# rda5708m.net
KiCad netlist of a schematic drawn in EAGLE
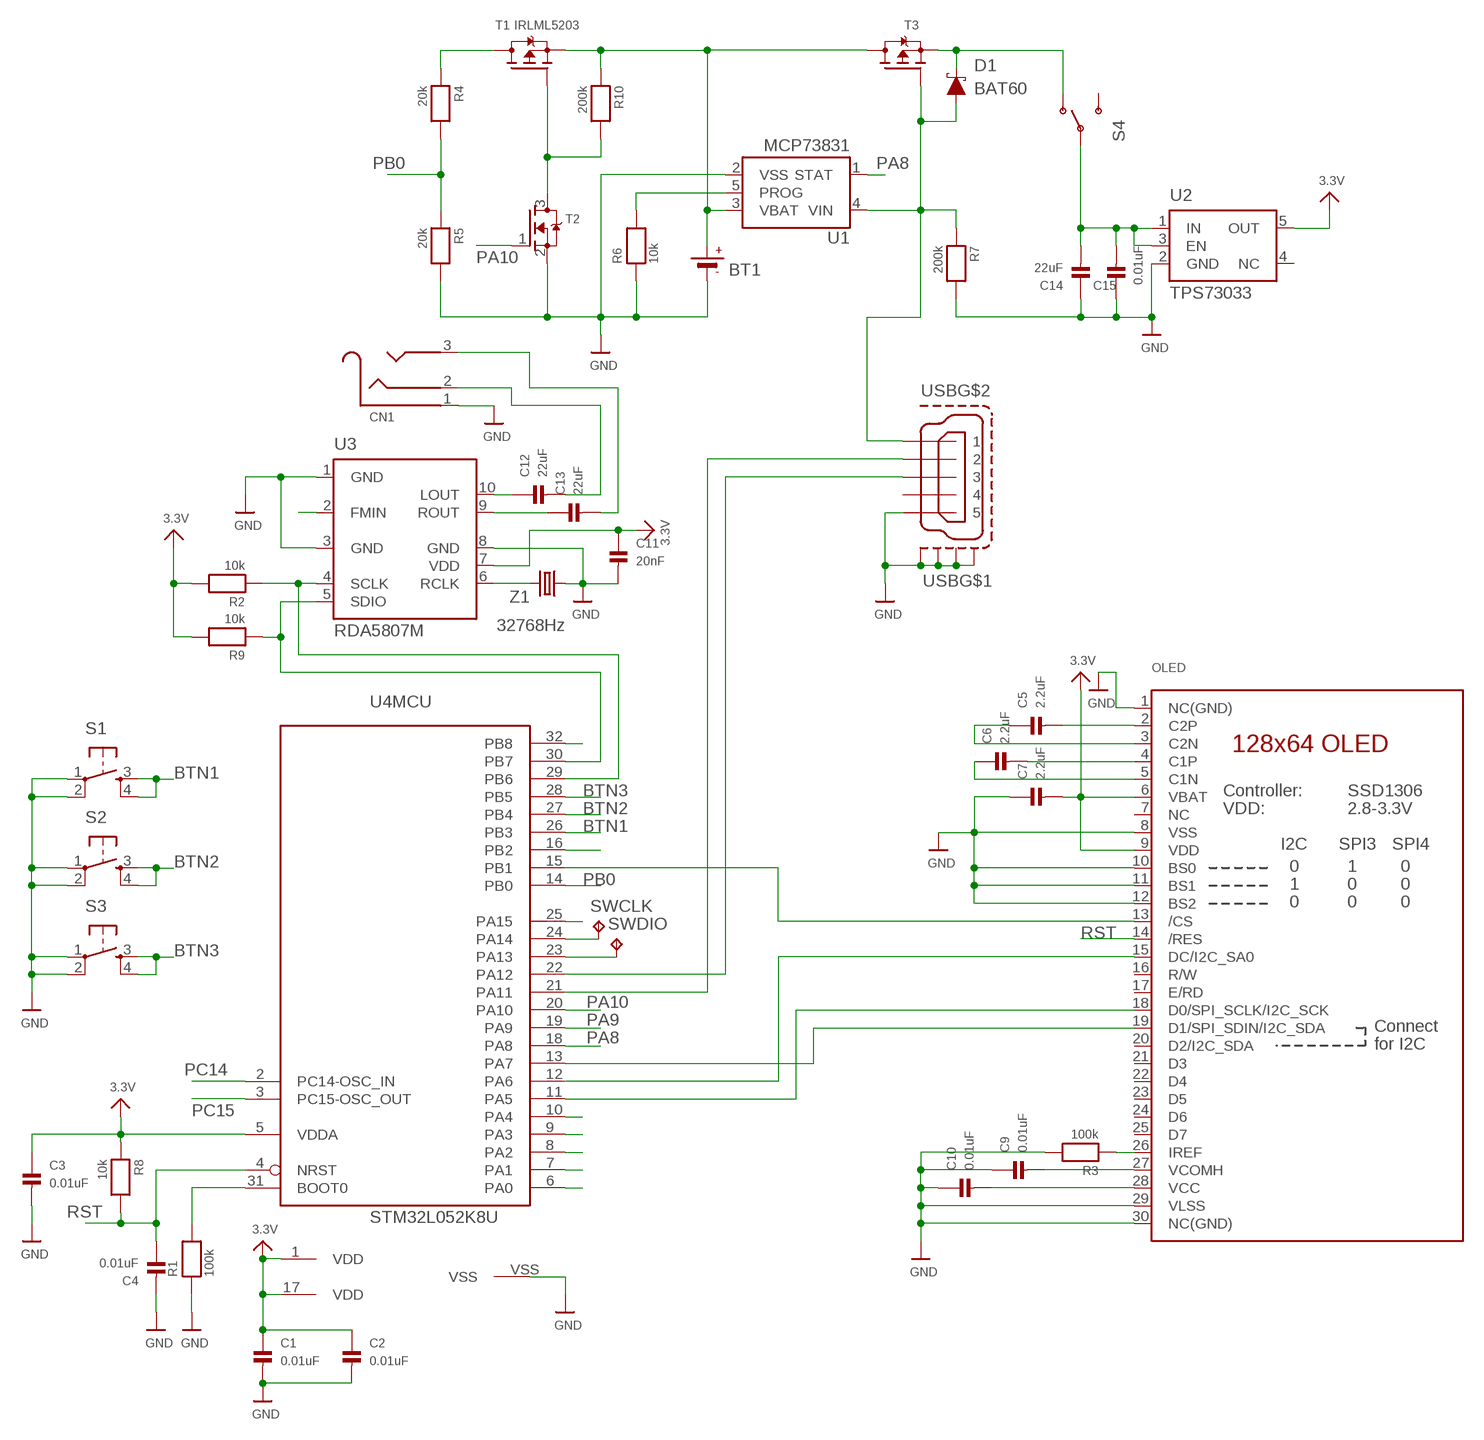
[diagram p0: schematic, sheet 1]

(export (version "E")
  (design (tool "Eeschema 10.0.6"))
  (components
    (comp (ref "BT1")
      (value "LiPo 4.2V")
      (footprint "eagle-import:JSTPH2")
      (libsource (lib "eagle-import") (part "BATTERY"))
    )
    (comp (ref "C1")
      (value "0.01uF")
      (footprint "eagle-import:0603")
      (libsource (lib "eagle-import") (part "CAP_CERAMIC0603"))
    )
    (comp (ref "C2")
      (value "0.01uF")
      (footprint "eagle-import:0603")
      (libsource (lib "eagle-import") (part "CAP_CERAMIC0603"))
    )
    (comp (ref "C3")
      (value "0.01uF")
      (footprint "eagle-import:0603")
      (libsource (lib "eagle-import") (part "CAP_CERAMIC0603"))
    )
    (comp (ref "C4")
      (value "0.01uF")
      (footprint "eagle-import:0603")
      (libsource (lib "eagle-import") (part "CAP_CERAMIC0603"))
    )
    (comp (ref "C5")
      (value "2.2uF")
      (footprint "eagle-import:0603")
      (libsource (lib "eagle-import") (part "CAP_CERAMIC0603"))
    )
    (comp (ref "C6")
      (value "2.2uF")
      (footprint "eagle-import:0603")
      (libsource (lib "eagle-import") (part "CAP_CERAMIC0603"))
    )
    (comp (ref "C7")
      (value "2.2uF")
      (footprint "eagle-import:0603")
      (libsource (lib "eagle-import") (part "CAP_CERAMIC0603"))
    )
    (comp (ref "C9")
      (value "0.01uF")
      (footprint "eagle-import:0603")
      (libsource (lib "eagle-import") (part "CAP_CERAMIC0603"))
    )
    (comp (ref "C10")
      (value "0.01uF")
      (footprint "eagle-import:0603")
      (libsource (lib "eagle-import") (part "CAP_CERAMIC0603"))
    )
    (comp (ref "C11")
      (value "20nF")
      (footprint "eagle-import:0603")
      (libsource (lib "eagle-import") (part "CAP_CERAMIC0603"))
    )
    (comp (ref "C12")
      (value "22uF")
      (footprint "eagle-import:0805")
      (libsource (lib "eagle-import") (part "CAP_CERAMIC0805"))
    )
    (comp (ref "C13")
      (value "22uF")
      (footprint "eagle-import:0805")
      (libsource (lib "eagle-import") (part "CAP_CERAMIC0805"))
    )
    (comp (ref "C14")
      (value "22uF")
      (footprint "eagle-import:0805")
      (libsource (lib "eagle-import") (part "CAP_CERAMIC0805"))
    )
    (comp (ref "C15")
      (value "0.01uF")
      (footprint "eagle-import:0603")
      (libsource (lib "eagle-import") (part "CAP_CERAMIC0603"))
    )
    (comp (ref "CN1")
      (value "AUDIO_3.5JACK")
      (footprint "eagle-import:AUDIO_3.5")
      (libsource (lib "eagle-import") (part "AUDIO_3.5JACK"))
    )
    (comp (ref "D1")
      (value "BAT60")
      (footprint "eagle-import:SOD-323")
      (libsource (lib "eagle-import") (part "DIODE-SCHOTTKY-BAT20J"))
    )
    (comp (ref "OLED")
      (value "DISP_OLED_UG-2864HSWEG012SIDE")
      (footprint "eagle-import:OLED0.96")
      (libsource (lib "eagle-import") (part "DISP_OLED_UG-2864HSWEG012SIDE"))
    )
    (comp (ref "R1")
      (value "100k")
      (footprint "eagle-import:0603")
      (libsource (lib "eagle-import") (part "RESISTOR0603"))
    )
    (comp (ref "R2")
      (value "10k")
      (footprint "eagle-import:0603")
      (libsource (lib "eagle-import") (part "RESISTOR0603"))
    )
    (comp (ref "R3")
      (value "100k")
      (footprint "eagle-import:0603")
      (libsource (lib "eagle-import") (part "RESISTOR0603"))
    )
    (comp (ref "R4")
      (value "20k")
      (footprint "eagle-import:0603")
      (libsource (lib "eagle-import") (part "RESISTOR0603"))
    )
    (comp (ref "R5")
      (value "20k")
      (footprint "eagle-import:0603")
      (libsource (lib "eagle-import") (part "RESISTOR0603"))
    )
    (comp (ref "R6")
      (value "10k")
      (footprint "eagle-import:0603")
      (libsource (lib "eagle-import") (part "RESISTOR0603"))
    )
    (comp (ref "R7")
      (value "200k")
      (footprint "eagle-import:0603")
      (libsource (lib "eagle-import") (part "RESISTOR0603"))
    )
    (comp (ref "R8")
      (value "10k")
      (footprint "eagle-import:0603")
      (libsource (lib "eagle-import") (part "RESISTOR0603"))
    )
    (comp (ref "R9")
      (value "10k")
      (footprint "eagle-import:0603")
      (libsource (lib "eagle-import") (part "RESISTOR0603"))
    )
    (comp (ref "R10")
      (value "200k")
      (footprint "eagle-import:0603")
      (libsource (lib "eagle-import") (part "RESISTOR0603"))
    )
    (comp (ref "S1")
      (value "TAC_SWITCH")
      (footprint "eagle-import:TACTILE-SWITCH-SMD45")
      (libsource (lib "eagle-import") (part "TAC_SWITCH"))
    )
    (comp (ref "S2")
      (value "TAC_SWITCH")
      (footprint "eagle-import:TACTILE-SWITCH-SMD45")
      (libsource (lib "eagle-import") (part "TAC_SWITCH"))
    )
    (comp (ref "S3")
      (value "TAC_SWITCH")
      (footprint "eagle-import:TACTILE-SWITCH-SMD45")
      (libsource (lib "eagle-import") (part "TAC_SWITCH"))
    )
    (comp (ref "S4")
      (value "SWITCH-SPDTPTH2")
      (footprint "eagle-import:SWITCH-DPDT")
      (libsource (lib "eagle-import") (part "SWITCH-SPDTPTH2"))
    )
    (comp (ref "SWCLK")
      (value "TPTP10R")
      (footprint "eagle-import:TP10R")
      (libsource (lib "eagle-import") (part "TPTP10R"))
    )
    (comp (ref "SWDIO")
      (value "TPTP10R")
      (footprint "eagle-import:TP10R")
      (libsource (lib "eagle-import") (part "TPTP10R"))
    )
    (comp (ref "T1")
      (value "IRLML5203")
      (footprint "eagle-import:SOT23-R")
      (libsource (lib "eagle-import") (part "MOSFET-P"))
    )
    (comp (ref "T2")
      (value "MOSFET-NREFLOW")
      (footprint "eagle-import:SOT23-R")
      (libsource (lib "eagle-import") (part "MOSFET-NREFLOW"))
    )
    (comp (ref "T3")
      (value "MOSFET-P")
      (footprint "eagle-import:SOT23-R")
      (libsource (lib "eagle-import") (part "MOSFET-P"))
    )
    (comp (ref "U1")
      (value "MCP73831")
      (footprint "eagle-import:SOT23-5")
      (libsource (lib "eagle-import") (part "MCP73831"))
    )
    (comp (ref "U2")
      (value "TPS73033")
      (footprint "eagle-import:SOT23-5")
      (libsource (lib "eagle-import") (part "TPS73033"))
    )
    (comp (ref "U3")
      (value "RDA5807M")
      (footprint "eagle-import:MSOP10")
      (libsource (lib "eagle-import") (part "RDA5807M"))
    )
    (comp (ref "U4")
      (value "STM32L052K8U")
      (footprint "eagle-import:UFQFPN32")
      (libsource (lib "eagle-import") (part "STM32L052KU8"))
    )
    (comp (ref "USB")
      (value "MICRO-USB-SHIELD-MICRO_USB-B_4.85_HORN")
      (footprint "eagle-import:MICRO_USB-B_4.85_HORN")
      (libsource (lib "eagle-import") (part "MICRO-USB-SHIELD-MICRO_USB-B_4.85_HORN"))
    )
    (comp (ref "Z1")
      (value "32768Hz")
      (footprint "eagle-import:TC26H-SMD")
      (libsource (lib "eagle-import") (part "CRYSTAL"))
    )
  )
  (nets
    (net (code "1") (name "/BTN1") (class "Default")
      (node (ref "S1") (pin "3") (pinfunction "3_3") (pintype "passive"))
      (node (ref "S1") (pin "4") (pinfunction "4_4") (pintype "passive"))
      (node (ref "U4") (pin "26") (pinfunction "PB3_26") (pintype "bidirectional"))
    )
    (net (code "2") (name "/BTN2") (class "Default")
      (node (ref "S2") (pin "3") (pinfunction "3_3") (pintype "passive"))
      (node (ref "S2") (pin "4") (pinfunction "4_4") (pintype "passive"))
      (node (ref "U4") (pin "27") (pinfunction "PB4_27") (pintype "bidirectional"))
    )
    (net (code "3") (name "/BTN3") (class "Default")
      (node (ref "S3") (pin "3") (pinfunction "3_3") (pintype "passive"))
      (node (ref "S3") (pin "4") (pinfunction "4_4") (pintype "passive"))
      (node (ref "U4") (pin "28") (pinfunction "PB5_28") (pintype "bidirectional"))
    )
    (net (code "4") (name "/PA8") (class "Default")
      (node (ref "U1") (pin "1") (pinfunction "STAT_1") (pintype "output"))
      (node (ref "U4") (pin "18") (pinfunction "PA8_18") (pintype "bidirectional"))
    )
    (net (code "5") (name "/PA9") (class "Default")
      (node (ref "U4") (pin "19") (pinfunction "PA9_19") (pintype "bidirectional"))
    )
    (net (code "6") (name "/PA10") (class "Default")
      (node (ref "T2") (pin "1") (pinfunction "G_1") (pintype "bidirectional"))
      (node (ref "U4") (pin "20") (pinfunction "PA10_20") (pintype "bidirectional"))
    )
    (net (code "7") (name "/PB0") (class "Default")
      (node (ref "R4") (pin "2") (pinfunction "2_2") (pintype "passive"))
      (node (ref "R5") (pin "1") (pinfunction "1_1") (pintype "passive"))
      (node (ref "U4") (pin "14") (pinfunction "PB0_14") (pintype "bidirectional"))
    )
    (net (code "8") (name "/PC14") (class "Default")
      (node (ref "U4") (pin "2") (pinfunction "PC14-OSC_IN_2") (pintype "bidirectional"))
    )
    (net (code "9") (name "/PC15") (class "Default")
      (node (ref "U4") (pin "3") (pinfunction "PC15-OSC_OUT_3") (pintype "bidirectional"))
    )
    (net (code "10") (name "/RST") (class "Default")
      (node (ref "C4") (pin "1") (pinfunction "P$1_1") (pintype "passive"))
      (node (ref "OLED") (pin "14") (pinfunction "/RES_14") (pintype "input"))
      (node (ref "R8") (pin "2") (pinfunction "2_2") (pintype "passive"))
      (node (ref "U4") (pin "4") (pinfunction "NRST_4") (pintype "bidirectional"))
    )
    (net (code "11") (name "3.3V") (class "Default")
      (node (ref "C1") (pin "1") (pinfunction "P$1_1") (pintype "passive"))
      (node (ref "C11") (pin "1") (pinfunction "P$1_1") (pintype "passive"))
      (node (ref "C2") (pin "1") (pinfunction "P$1_1") (pintype "passive"))
      (node (ref "C3") (pin "1") (pinfunction "P$1_1") (pintype "passive"))
      (node (ref "C7") (pin "2") (pinfunction "P$2_2") (pintype "passive"))
      (node (ref "OLED") (pin "6") (pinfunction "VBAT_6") (pintype "input"))
      (node (ref "OLED") (pin "9") (pinfunction "VDD_9") (pintype "power_in"))
      (node (ref "R2") (pin "2") (pinfunction "2_2") (pintype "passive"))
      (node (ref "R8") (pin "1") (pinfunction "1_1") (pintype "passive"))
      (node (ref "R9") (pin "2") (pinfunction "2_2") (pintype "passive"))
      (node (ref "U2") (pin "5") (pinfunction "OUT_5") (pintype "passive"))
      (node (ref "U3") (pin "7") (pinfunction "VDD_7") (pintype "power_in"))
      (node (ref "U4") (pin "1") (pinfunction "VDD_1") (pintype "power_in"))
      (node (ref "U4") (pin "17") (pinfunction "VDD_17") (pintype "power_in"))
      (node (ref "U4") (pin "5") (pinfunction "VDDA_5") (pintype "power_in"))
    )
    (net (code "12") (name "GND") (class "Default")
      (node (ref "BT1") (pin "1") (pinfunction "-_1") (pintype "passive"))
      (node (ref "C1") (pin "2") (pinfunction "P$2_2") (pintype "passive"))
      (node (ref "C10") (pin "1") (pinfunction "P$1_1") (pintype "passive"))
      (node (ref "C11") (pin "2") (pinfunction "P$2_2") (pintype "passive"))
      (node (ref "C14") (pin "1") (pinfunction "P$1_1") (pintype "passive"))
      (node (ref "C15") (pin "1") (pinfunction "P$1_1") (pintype "passive"))
      (node (ref "C2") (pin "2") (pinfunction "P$2_2") (pintype "passive"))
      (node (ref "C3") (pin "2") (pinfunction "P$2_2") (pintype "passive"))
      (node (ref "C4") (pin "2") (pinfunction "P$2_2") (pintype "passive"))
      (node (ref "C7") (pin "1") (pinfunction "P$1_1") (pintype "passive"))
      (node (ref "C9") (pin "1") (pinfunction "P$1_1") (pintype "passive"))
      (node (ref "CN1") (pin "1") (pinfunction "P$1_1") (pintype "bidirectional"))
      (node (ref "OLED") (pin "1") (pinfunction "NC(GND)_1") (pintype "input"))
      (node (ref "OLED") (pin "10") (pinfunction "BS0_10") (pintype "input"))
      (node (ref "OLED") (pin "11") (pinfunction "BS1_11") (pintype "input"))
      (node (ref "OLED") (pin "12") (pinfunction "BS2_12") (pintype "input"))
      (node (ref "OLED") (pin "29") (pinfunction "VLSS_29") (pintype "power_in"))
      (node (ref "OLED") (pin "30") (pinfunction "NC(GND)_30") (pintype "input"))
      (node (ref "OLED") (pin "8") (pinfunction "VSS_8") (pintype "power_in"))
      (node (ref "R1") (pin "1") (pinfunction "1_1") (pintype "passive"))
      (node (ref "R3") (pin "2") (pinfunction "2_2") (pintype "passive"))
      (node (ref "R5") (pin "2") (pinfunction "2_2") (pintype "passive"))
      (node (ref "R6") (pin "1") (pinfunction "1_1") (pintype "passive"))
      (node (ref "R7") (pin "2") (pinfunction "2_2") (pintype "passive"))
      (node (ref "S1") (pin "1") (pinfunction "1_1") (pintype "passive"))
      (node (ref "S1") (pin "2") (pinfunction "2_2") (pintype "passive"))
      (node (ref "S2") (pin "1") (pinfunction "1_1") (pintype "passive"))
      (node (ref "S2") (pin "2") (pinfunction "2_2") (pintype "passive"))
      (node (ref "S3") (pin "1") (pinfunction "1_1") (pintype "passive"))
      (node (ref "S3") (pin "2") (pinfunction "2_2") (pintype "passive"))
      (node (ref "T2") (pin "2") (pinfunction "S_2") (pintype "bidirectional"))
      (node (ref "U1") (pin "2") (pinfunction "VSS_2") (pintype "power_in"))
      (node (ref "U2") (pin "2") (pinfunction "GND_2") (pintype "power_in"))
      (node (ref "U3") (pin "1") (pinfunction "GND_1") (pintype "power_in"))
      (node (ref "U3") (pin "3") (pinfunction "GND_3") (pintype "power_in"))
      (node (ref "U3") (pin "8") (pinfunction "GND_8") (pintype "power_in"))
      (node (ref "U4") (pin "VSS") (pinfunction "VSS_VSS") (pintype "power_in"))
      (node (ref "USB") (pin "5") (pinfunction "5_5") (pintype "input"))
      (node (ref "USB") (pin "M1") (pinfunction "S1_M1") (pintype "passive"))
      (node (ref "USB") (pin "M2") (pinfunction "S2_M2") (pintype "passive"))
      (node (ref "USB") (pin "M3") (pinfunction "S3_M3") (pintype "passive"))
      (node (ref "USB") (pin "M4") (pinfunction "S4_M4") (pintype "passive"))
      (node (ref "Z1") (pin "P$1") (pinfunction "1_P$1") (pintype "passive"))
    )
    (net (code "13") (name "Net-(BT1-+)") (class "Default")
      (node (ref "BT1") (pin "2") (pinfunction "+_2") (pintype "passive"))
      (node (ref "R10") (pin "1") (pinfunction "1_1") (pintype "passive"))
      (node (ref "T1") (pin "2") (pinfunction "S_2") (pintype "passive"))
      (node (ref "T3") (pin "3") (pinfunction "D_3") (pintype "passive"))
      (node (ref "U1") (pin "3") (pinfunction "VBAT_3") (pintype "power_in"))
    )
    (net (code "14") (name "Net-(C5-P$1)") (class "Default")
      (node (ref "C5") (pin "1") (pinfunction "P$1_1") (pintype "passive"))
      (node (ref "OLED") (pin "3") (pinfunction "C2N_3") (pintype "input"))
    )
    (net (code "15") (name "Net-(C5-P$2)") (class "Default")
      (node (ref "C5") (pin "2") (pinfunction "P$2_2") (pintype "passive"))
      (node (ref "OLED") (pin "2") (pinfunction "C2P_2") (pintype "input"))
    )
    (net (code "16") (name "Net-(C6-P$1)") (class "Default")
      (node (ref "C6") (pin "1") (pinfunction "P$1_1") (pintype "passive"))
      (node (ref "OLED") (pin "5") (pinfunction "C1N_5") (pintype "input"))
    )
    (net (code "17") (name "Net-(C6-P$2)") (class "Default")
      (node (ref "C6") (pin "2") (pinfunction "P$2_2") (pintype "passive"))
      (node (ref "OLED") (pin "4") (pinfunction "C1P_4") (pintype "input"))
    )
    (net (code "18") (name "Net-(C9-P$2)") (class "Default")
      (node (ref "C9") (pin "2") (pinfunction "P$2_2") (pintype "passive"))
      (node (ref "OLED") (pin "27") (pinfunction "VCOMH_27") (pintype "output"))
    )
    (net (code "19") (name "Net-(C10-P$2)") (class "Default")
      (node (ref "C10") (pin "2") (pinfunction "P$2_2") (pintype "passive"))
      (node (ref "OLED") (pin "28") (pinfunction "VCC_28") (pintype "power_in"))
    )
    (net (code "20") (name "Net-(C12-P$1)") (class "Default")
      (node (ref "C12") (pin "1") (pinfunction "P$1_1") (pintype "passive"))
      (node (ref "U3") (pin "10") (pinfunction "LOUT_10") (pintype "input"))
    )
    (net (code "21") (name "Net-(C12-P$2)") (class "Default")
      (node (ref "C12") (pin "2") (pinfunction "P$2_2") (pintype "passive"))
      (node (ref "CN1") (pin "2") (pinfunction "P$2_2") (pintype "bidirectional"))
    )
    (net (code "22") (name "Net-(C13-P$1)") (class "Default")
      (node (ref "C13") (pin "1") (pinfunction "P$1_1") (pintype "passive"))
      (node (ref "U3") (pin "9") (pinfunction "ROUT_9") (pintype "output"))
    )
    (net (code "23") (name "Net-(C13-P$2)") (class "Default")
      (node (ref "C13") (pin "2") (pinfunction "P$2_2") (pintype "passive"))
      (node (ref "CN1") (pin "3") (pinfunction "P$3_3") (pintype "bidirectional"))
    )
    (net (code "24") (name "Net-(C14-P$2)") (class "Default")
      (node (ref "C14") (pin "2") (pinfunction "P$2_2") (pintype "passive"))
      (node (ref "C15") (pin "2") (pinfunction "P$2_2") (pintype "passive"))
      (node (ref "S4") (pin "2") (pinfunction "P_2") (pintype "passive"))
      (node (ref "U2") (pin "1") (pinfunction "IN_1") (pintype "passive"))
      (node (ref "U2") (pin "3") (pinfunction "EN_3") (pintype "input"))
    )
    (net (code "25") (name "Net-(OLED-D0{slash}SPI_SCLK{slash}I2C_SCK)") (class "Default")
      (node (ref "OLED") (pin "18") (pinfunction "D0/SPI_SCLK/I2C_SCK_18") (pintype "bidirectional"))
      (node (ref "U4") (pin "11") (pinfunction "PA5_11") (pintype "bidirectional"))
    )
    (net (code "26") (name "Net-(OLED-D1{slash}SPI_SDIN{slash}I2C_SDA)") (class "Default")
      (node (ref "OLED") (pin "19") (pinfunction "D1/SPI_SDIN/I2C_SDA_19") (pintype "bidirectional"))
      (node (ref "U4") (pin "13") (pinfunction "PA7_13") (pintype "bidirectional"))
    )
    (net (code "27") (name "Net-(OLED-DC{slash}I2C_SA0)") (class "Default")
      (node (ref "OLED") (pin "15") (pinfunction "DC/I2C_SA0_15") (pintype "input"))
      (node (ref "U4") (pin "12") (pinfunction "PA6_12") (pintype "bidirectional"))
    )
    (net (code "28") (name "Net-(OLED-IREF)") (class "Default")
      (node (ref "OLED") (pin "26") (pinfunction "IREF_26") (pintype "input"))
      (node (ref "R3") (pin "1") (pinfunction "1_1") (pintype "passive"))
    )
    (net (code "29") (name "Net-(OLED-{slash}CS)") (class "Default")
      (node (ref "OLED") (pin "13") (pinfunction "/CS_13") (pintype "input"))
      (node (ref "U4") (pin "15") (pinfunction "PB1_15") (pintype "bidirectional"))
    )
    (net (code "30") (name "Net-(S4-O)") (class "Default")
      (node (ref "D1") (pin "C") (pinfunction "C_C") (pintype "passive"))
      (node (ref "S4") (pin "1") (pinfunction "O_1") (pintype "passive"))
      (node (ref "T3") (pin "2") (pinfunction "S_2") (pintype "passive"))
    )
    (net (code "31") (name "Net-(T1-D)") (class "Default")
      (node (ref "R4") (pin "1") (pinfunction "1_1") (pintype "passive"))
      (node (ref "T1") (pin "3") (pinfunction "D_3") (pintype "passive"))
    )
    (net (code "32") (name "Net-(T1-G)") (class "Default")
      (node (ref "R10") (pin "2") (pinfunction "2_2") (pintype "passive"))
      (node (ref "T1") (pin "1") (pinfunction "G_1") (pintype "passive"))
      (node (ref "T2") (pin "3") (pinfunction "D_3") (pintype "bidirectional"))
    )
    (net (code "33") (name "Net-(T3-G)") (class "Default")
      (node (ref "D1") (pin "A") (pinfunction "A_A") (pintype "passive"))
      (node (ref "R7") (pin "1") (pinfunction "1_1") (pintype "passive"))
      (node (ref "T3") (pin "1") (pinfunction "G_1") (pintype "passive"))
      (node (ref "U1") (pin "4") (pinfunction "VIN_4") (pintype "power_in"))
      (node (ref "USB") (pin "1") (pinfunction "1_1") (pintype "input"))
    )
    (net (code "34") (name "Net-(U1-PROG)") (class "Default")
      (node (ref "R6") (pin "2") (pinfunction "2_2") (pintype "passive"))
      (node (ref "U1") (pin "5") (pinfunction "PROG_5") (pintype "input"))
    )
    (net (code "35") (name "Net-(U3-RCLK)") (class "Default")
      (node (ref "U3") (pin "6") (pinfunction "RCLK_6") (pintype "bidirectional"))
      (node (ref "Z1") (pin "P$2") (pinfunction "2_P$2") (pintype "passive"))
    )
    (net (code "36") (name "Net-(U3-SCLK)") (class "Default")
      (node (ref "R2") (pin "1") (pinfunction "1_1") (pintype "passive"))
      (node (ref "U3") (pin "4") (pinfunction "SCLK_4") (pintype "power_in"))
      (node (ref "U4") (pin "29") (pinfunction "PB6_29") (pintype "bidirectional"))
    )
    (net (code "37") (name "Net-(U3-SDIO)") (class "Default")
      (node (ref "R9") (pin "1") (pinfunction "1_1") (pintype "passive"))
      (node (ref "U3") (pin "5") (pinfunction "SDIO_5") (pintype "power_in"))
      (node (ref "U4") (pin "30") (pinfunction "PB7_30") (pintype "bidirectional"))
    )
    (net (code "38") (name "Net-(U4A-BOOT0)") (class "Default")
      (node (ref "R1") (pin "2") (pinfunction "2_2") (pintype "passive"))
      (node (ref "U4") (pin "31") (pinfunction "BOOT0_31") (pintype "input"))
    )
    (net (code "39") (name "Net-(U4A-PA11)") (class "Default")
      (node (ref "U4") (pin "21") (pinfunction "PA11_21") (pintype "bidirectional"))
      (node (ref "USB") (pin "2") (pinfunction "2_2") (pintype "input"))
    )
    (net (code "40") (name "Net-(U4A-PA12)") (class "Default")
      (node (ref "U4") (pin "22") (pinfunction "PA12_22") (pintype "bidirectional"))
      (node (ref "USB") (pin "3") (pinfunction "3_3") (pintype "input"))
    )
    (net (code "41") (name "Net-(U4A-PA13)") (class "Default")
      (node (ref "SWDIO") (pin "TP") (pinfunction "TP_TP") (pintype "input"))
      (node (ref "U4") (pin "23") (pinfunction "PA13_23") (pintype "bidirectional"))
    )
    (net (code "42") (name "Net-(U4A-PA14)") (class "Default")
      (node (ref "SWCLK") (pin "TP") (pinfunction "TP_TP") (pintype "input"))
      (node (ref "U4") (pin "24") (pinfunction "PA14_24") (pintype "bidirectional"))
    )
    (net (code "43") (name "unconnected-(OLED-D2{slash}I2C_SDA-Pad20)") (class "Default")
      (node (ref "OLED") (pin "20") (pinfunction "D2/I2C_SDA_20") (pintype "bidirectional"))
    )
    (net (code "44") (name "unconnected-(OLED-D3-Pad21)") (class "Default")
      (node (ref "OLED") (pin "21") (pinfunction "D3_21") (pintype "bidirectional"))
    )
    (net (code "45") (name "unconnected-(OLED-D4-Pad22)") (class "Default")
      (node (ref "OLED") (pin "22") (pinfunction "D4_22") (pintype "bidirectional"))
    )
    (net (code "46") (name "unconnected-(OLED-D5-Pad23)") (class "Default")
      (node (ref "OLED") (pin "23") (pinfunction "D5_23") (pintype "bidirectional"))
    )
    (net (code "47") (name "unconnected-(OLED-D6-Pad24)") (class "Default")
      (node (ref "OLED") (pin "24") (pinfunction "D6_24") (pintype "bidirectional"))
    )
    (net (code "48") (name "unconnected-(OLED-D7-Pad25)") (class "Default")
      (node (ref "OLED") (pin "25") (pinfunction "D7_25") (pintype "bidirectional"))
    )
    (net (code "49") (name "unconnected-(OLED-E{slash}RD-Pad17)") (class "Default")
      (node (ref "OLED") (pin "17") (pinfunction "E/RD_17") (pintype "input"))
    )
    (net (code "50") (name "unconnected-(OLED-NC-Pad7)") (class "Default")
      (node (ref "OLED") (pin "7") (pinfunction "NC_7") (pintype "no_connect"))
    )
    (net (code "51") (name "unconnected-(OLED-R{slash}W-Pad16)") (class "Default")
      (node (ref "OLED") (pin "16") (pinfunction "R/W_16") (pintype "input"))
    )
    (net (code "52") (name "unconnected-(S4-S-Pad3)") (class "Default")
      (node (ref "S4") (pin "3") (pinfunction "S_3") (pintype "passive"))
    )
    (net (code "53") (name "unconnected-(U2-NC-Pad4)") (class "Default")
      (node (ref "U2") (pin "4") (pinfunction "NC_4") (pintype "no_connect"))
    )
    (net (code "54") (name "unconnected-(U3-FMIN-Pad2)") (class "Default")
      (node (ref "U3") (pin "2") (pinfunction "FMIN_2") (pintype "input"))
    )
    (net (code "55") (name "unconnected-(U4A-PA0-Pad6)") (class "Default")
      (node (ref "U4") (pin "6") (pinfunction "PA0_6") (pintype "bidirectional"))
    )
    (net (code "56") (name "unconnected-(U4A-PA1-Pad7)") (class "Default")
      (node (ref "U4") (pin "7") (pinfunction "PA1_7") (pintype "bidirectional"))
    )
    (net (code "57") (name "unconnected-(U4A-PA2-Pad8)") (class "Default")
      (node (ref "U4") (pin "8") (pinfunction "PA2_8") (pintype "bidirectional"))
    )
    (net (code "58") (name "unconnected-(U4A-PA3-Pad9)") (class "Default")
      (node (ref "U4") (pin "9") (pinfunction "PA3_9") (pintype "bidirectional"))
    )
    (net (code "59") (name "unconnected-(U4A-PA4-Pad10)") (class "Default")
      (node (ref "U4") (pin "10") (pinfunction "PA4_10") (pintype "bidirectional"))
    )
    (net (code "60") (name "unconnected-(U4A-PA15-Pad25)") (class "Default")
      (node (ref "U4") (pin "25") (pinfunction "PA15_25") (pintype "bidirectional"))
    )
    (net (code "61") (name "unconnected-(U4A-PB2-Pad16)") (class "Default")
      (node (ref "U4") (pin "16") (pinfunction "PB2_16") (pintype "bidirectional"))
    )
    (net (code "62") (name "unconnected-(U4A-PB8-Pad32)") (class "Default")
      (node (ref "U4") (pin "32") (pinfunction "PB8_32") (pintype "bidirectional"))
    )
    (net (code "63") (name "unconnected-(USB-Pad4)") (class "Default")
      (node (ref "USB") (pin "4") (pinfunction "4_4") (pintype "input"))
    )
  )
)
